# EEPROM_Temp.net
KiCad netlist of a schematic drawn in Altium Designer
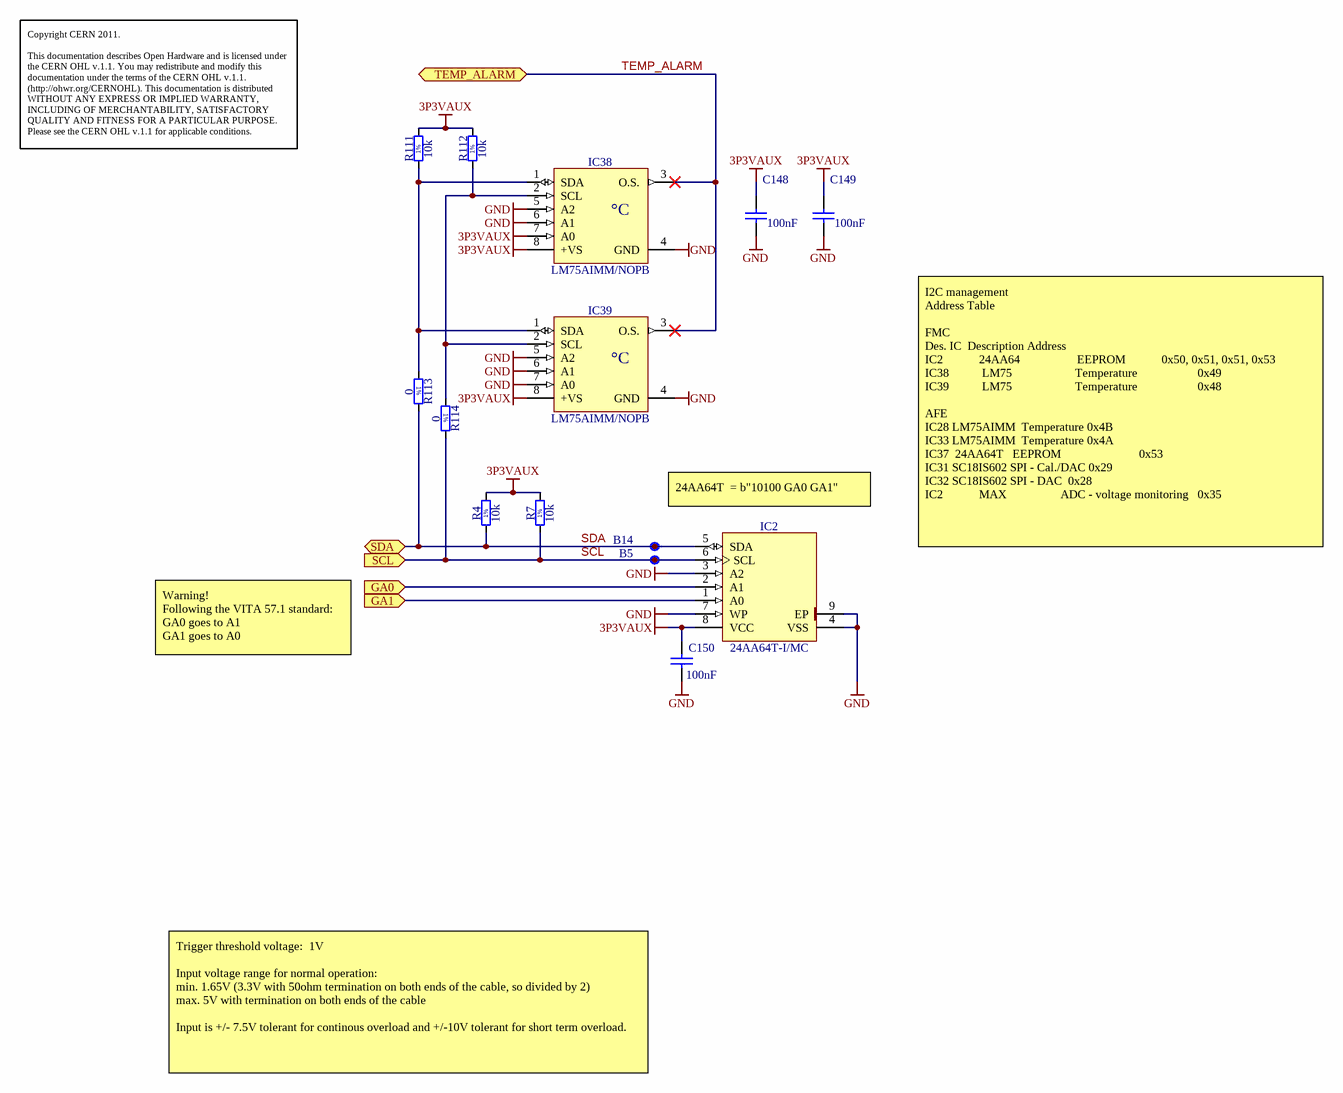
[diagram p0: EEPROM_Temp.SchDoc]

(export (version "E")
  (design (tool "Eeschema 10.0.6"))
  (components
    (comp (ref "B5")
      (value "SMD Pad")
      (footprint "C100")
      (description "Through Hole Pad")
      (fields (field (name "PART NUMBER") "SMD_PAD_D1MM") (field (name "AUTHOR") "CERN DEM JLC"))
      (libsource (lib "Eletro-mechanical") (part "Single SMD Pad (Round)"))
    )
    (comp (ref "B14")
      (value "SMD Pad")
      (footprint "C100")
      (description "Through Hole Pad")
      (fields (field (name "PART NUMBER") "SMD_PAD_D1MM") (field (name "AUTHOR") "CERN DEM JLC"))
      (libsource (lib "Eletro-mechanical") (part "Single SMD Pad (Round)"))
    )
    (comp (ref "C148")
      (value "100nF")
      (footprint "CAPC1005X55N")
      (description "Non-polarised capacitor")
      (fields
        (field (name "PART NUMBER") "CC0402_100NF_16V_10%_X5R")
        (field (name "VOLTAGE") "16V")
        (field (name "AUTHOR") "CERN DEM JLC")
      )
      (libsource (lib "Capacitors") (part "Capacitor - non polarized"))
    )
    (comp (ref "C149")
      (value "100nF")
      (footprint "CAPC1005X55N")
      (description "Non-polarised capacitor")
      (fields
        (field (name "PART NUMBER") "CC0402_100NF_16V_10%_X5R")
        (field (name "VOLTAGE") "16V")
        (field (name "AUTHOR") "CERN DEM JLC")
      )
      (libsource (lib "Capacitors") (part "Capacitor - non polarized"))
    )
    (comp (ref "C150")
      (value "100nF")
      (footprint "CAPC1005X55N")
      (description "Non-polarised capacitor")
      (fields
        (field (name "PART NUMBER") "CC0402_100NF_16V_10%_X5R")
        (field (name "VOLTAGE") "16V")
        (field (name "AUTHOR") "CERN DEM JLC")
      )
      (libsource (lib "Capacitors") (part "Capacitor - non polarized"))
    )
    (comp (ref "IC2")
      (value "24AA64T-I/MC")
      (footprint "SON50P300X200X100-9N-R175X155")
      (description "1.7V-5.5V 64K I2C Serial EEPROM")
      (fields (field (name "MANUFACTURER") "MICROCHIP TECHNOLOGY") (field (name "AUTHOR") "CERN DEM JLC"))
      (libsource (lib "ICs And Semiconductors") (part "24AA64T-I/MC"))
    )
    (comp (ref "IC38")
      (value "LM75AIMM/NOPB")
      (footprint "SOP65P490X109-8N")
      (description "Digital Temperature Sensor and Thermal Watchdog with Two-Wire Interface")
      (fields (field (name "MANUFACTURER") "TEXAS INSTRUMENTS") (field (name "AUTHOR") "CERN DEM JLC"))
      (libsource (lib "ICs And Semiconductors") (part "LM75"))
    )
    (comp (ref "IC39")
      (value "LM75AIMM/NOPB")
      (footprint "SOP65P490X109-8N")
      (description "Digital Temperature Sensor and Thermal Watchdog with Two-Wire Interface")
      (fields (field (name "MANUFACTURER") "TEXAS INSTRUMENTS") (field (name "AUTHOR") "CERN DEM JLC"))
      (libsource (lib "ICs And Semiconductors") (part "LM75"))
    )
    (comp (ref "R4")
      (value "10k")
      (footprint "RESC1005X40N")
      (description "Resistor - 1%")
      (fields
        (field (name "PART NUMBER") "R0402_10K_1%_0.0625W_100PPM")
        (field (name "POWER") "0.0625W")
        (field (name "AUTHOR") "CERN DEM JLC")
      )
      (libsource (lib "Resistors") (part "Resistor - 1%"))
    )
    (comp (ref "R7")
      (value "10k")
      (footprint "RESC1005X40N")
      (description "Resistor - 1%")
      (fields
        (field (name "PART NUMBER") "R0402_10K_1%_0.0625W_100PPM")
        (field (name "POWER") "0.0625W")
        (field (name "AUTHOR") "CERN DEM JLC")
      )
      (libsource (lib "Resistors") (part "Resistor - 1%"))
    )
    (comp (ref "R111")
      (value "10k")
      (footprint "RESC1005X40N")
      (description "Resistor - 1%")
      (fields
        (field (name "PART NUMBER") "R0402_10K_1%_0.0625W_100PPM")
        (field (name "POWER") "0.0625W")
        (field (name "AUTHOR") "CERN DEM JLC")
      )
      (libsource (lib "Resistors") (part "Resistor - 1%"))
    )
    (comp (ref "R112")
      (value "10k")
      (footprint "RESC1005X40N")
      (description "Resistor - 1%")
      (fields
        (field (name "PART NUMBER") "R0402_10K_1%_0.0625W_100PPM")
        (field (name "POWER") "0.0625W")
        (field (name "AUTHOR") "CERN DEM JLC")
      )
      (libsource (lib "Resistors") (part "Resistor - 1%"))
    )
    (comp (ref "R113")
      (value "0")
      (footprint "RESC1005X40N")
      (description "Resistor - 1%")
      (fields
        (field (name "PART NUMBER") "R0402_0R_JUMPER")
        (field (name "MANUFACTURER") "GENERIC")
        (field (name "AUTHOR") "CERN DEM JLC")
      )
      (libsource (lib "Resistors") (part "Resistor - 1%"))
    )
    (comp (ref "R114")
      (value "0")
      (footprint "RESC1005X40N")
      (description "Resistor - 1%")
      (fields
        (field (name "PART NUMBER") "R0402_0R_JUMPER")
        (field (name "MANUFACTURER") "GENERIC")
        (field (name "AUTHOR") "CERN DEM JLC")
      )
      (libsource (lib "Resistors") (part "Resistor - 1%"))
    )
  )
  (nets
    (net (code "1") (name "/GA0") (class "Default")
      (node (ref "IC2") (pin "2") (pinfunction "A1_2") (pintype "input"))
    )
    (net (code "2") (name "/GA1") (class "Default")
      (node (ref "IC2") (pin "1") (pinfunction "A0_1") (pintype "input"))
    )
    (net (code "3") (name "/SCL") (class "Default")
      (node (ref "B5") (pin "1") (pinfunction "1_1") (pintype "bidirectional"))
      (node (ref "IC2") (pin "6") (pinfunction "SCL_6") (pintype "input"))
      (node (ref "R114") (pin "2") (pinfunction "2_2") (pintype "passive"))
      (node (ref "R7") (pin "1") (pinfunction "1_1") (pintype "passive"))
    )
    (net (code "4") (name "/SDA") (class "Default")
      (node (ref "B14") (pin "1") (pinfunction "1_1") (pintype "bidirectional"))
      (node (ref "IC2") (pin "5") (pinfunction "SDA_5") (pintype "bidirectional"))
      (node (ref "R113") (pin "2") (pinfunction "2_2") (pintype "passive"))
      (node (ref "R4") (pin "1") (pinfunction "1_1") (pintype "passive"))
    )
    (net (code "5") (name "/TEMP_ALARM") (class "Default")
      (node (ref "IC38") (pin "3") (pinfunction "O.S._3") (pintype "output"))
      (node (ref "IC39") (pin "3") (pinfunction "O.S._3") (pintype "output"))
    )
    (net (code "6") (name "3P3VAUX") (class "Default")
      (node (ref "C148") (pin "1") (pinfunction "1_1") (pintype "passive"))
      (node (ref "C149") (pin "1") (pinfunction "1_1") (pintype "passive"))
      (node (ref "C150") (pin "1") (pinfunction "1_1") (pintype "passive"))
      (node (ref "IC2") (pin "8") (pinfunction "VCC_8") (pintype "power_in"))
      (node (ref "IC38") (pin "7") (pinfunction "A0_7") (pintype "input"))
      (node (ref "IC38") (pin "8") (pinfunction "+VS_8") (pintype "power_in"))
      (node (ref "IC39") (pin "8") (pinfunction "+VS_8") (pintype "power_in"))
      (node (ref "R111") (pin "2") (pinfunction "2_2") (pintype "passive"))
      (node (ref "R112") (pin "2") (pinfunction "2_2") (pintype "passive"))
      (node (ref "R4") (pin "2") (pinfunction "2_2") (pintype "passive"))
      (node (ref "R7") (pin "2") (pinfunction "2_2") (pintype "passive"))
    )
    (net (code "7") (name "GND") (class "Default")
      (node (ref "C148") (pin "2") (pinfunction "2_2") (pintype "passive"))
      (node (ref "C149") (pin "2") (pinfunction "2_2") (pintype "passive"))
      (node (ref "C150") (pin "2") (pinfunction "2_2") (pintype "passive"))
      (node (ref "IC2") (pin "3") (pinfunction "A2_3") (pintype "input"))
      (node (ref "IC2") (pin "4") (pinfunction "VSS_4") (pintype "power_in"))
      (node (ref "IC2") (pin "7") (pinfunction "WP_7") (pintype "input"))
      (node (ref "IC2") (pin "9") (pinfunction "EP_9") (pintype "power_in"))
      (node (ref "IC38") (pin "4") (pinfunction "GND_4") (pintype "power_in"))
      (node (ref "IC38") (pin "5") (pinfunction "A2_5") (pintype "input"))
      (node (ref "IC38") (pin "6") (pinfunction "A1_6") (pintype "input"))
      (node (ref "IC39") (pin "4") (pinfunction "GND_4") (pintype "power_in"))
      (node (ref "IC39") (pin "5") (pinfunction "A2_5") (pintype "input"))
      (node (ref "IC39") (pin "6") (pinfunction "A1_6") (pintype "input"))
      (node (ref "IC39") (pin "7") (pinfunction "A0_7") (pintype "input"))
    )
    (net (code "8") (name "Net-(IC38-SCL)") (class "Default")
      (node (ref "IC38") (pin "2") (pinfunction "SCL_2") (pintype "input"))
      (node (ref "IC39") (pin "2") (pinfunction "SCL_2") (pintype "input"))
      (node (ref "R112") (pin "1") (pinfunction "1_1") (pintype "passive"))
      (node (ref "R114") (pin "1") (pinfunction "1_1") (pintype "passive"))
    )
    (net (code "9") (name "Net-(IC38-SDA)") (class "Default")
      (node (ref "IC38") (pin "1") (pinfunction "SDA_1") (pintype "bidirectional"))
      (node (ref "IC39") (pin "1") (pinfunction "SDA_1") (pintype "bidirectional"))
      (node (ref "R111") (pin "1") (pinfunction "1_1") (pintype "passive"))
      (node (ref "R113") (pin "1") (pinfunction "1_1") (pintype "passive"))
    )
  )
)
